# FM_Transmitter.net
KiCad netlist of a schematic drawn in EAGLE
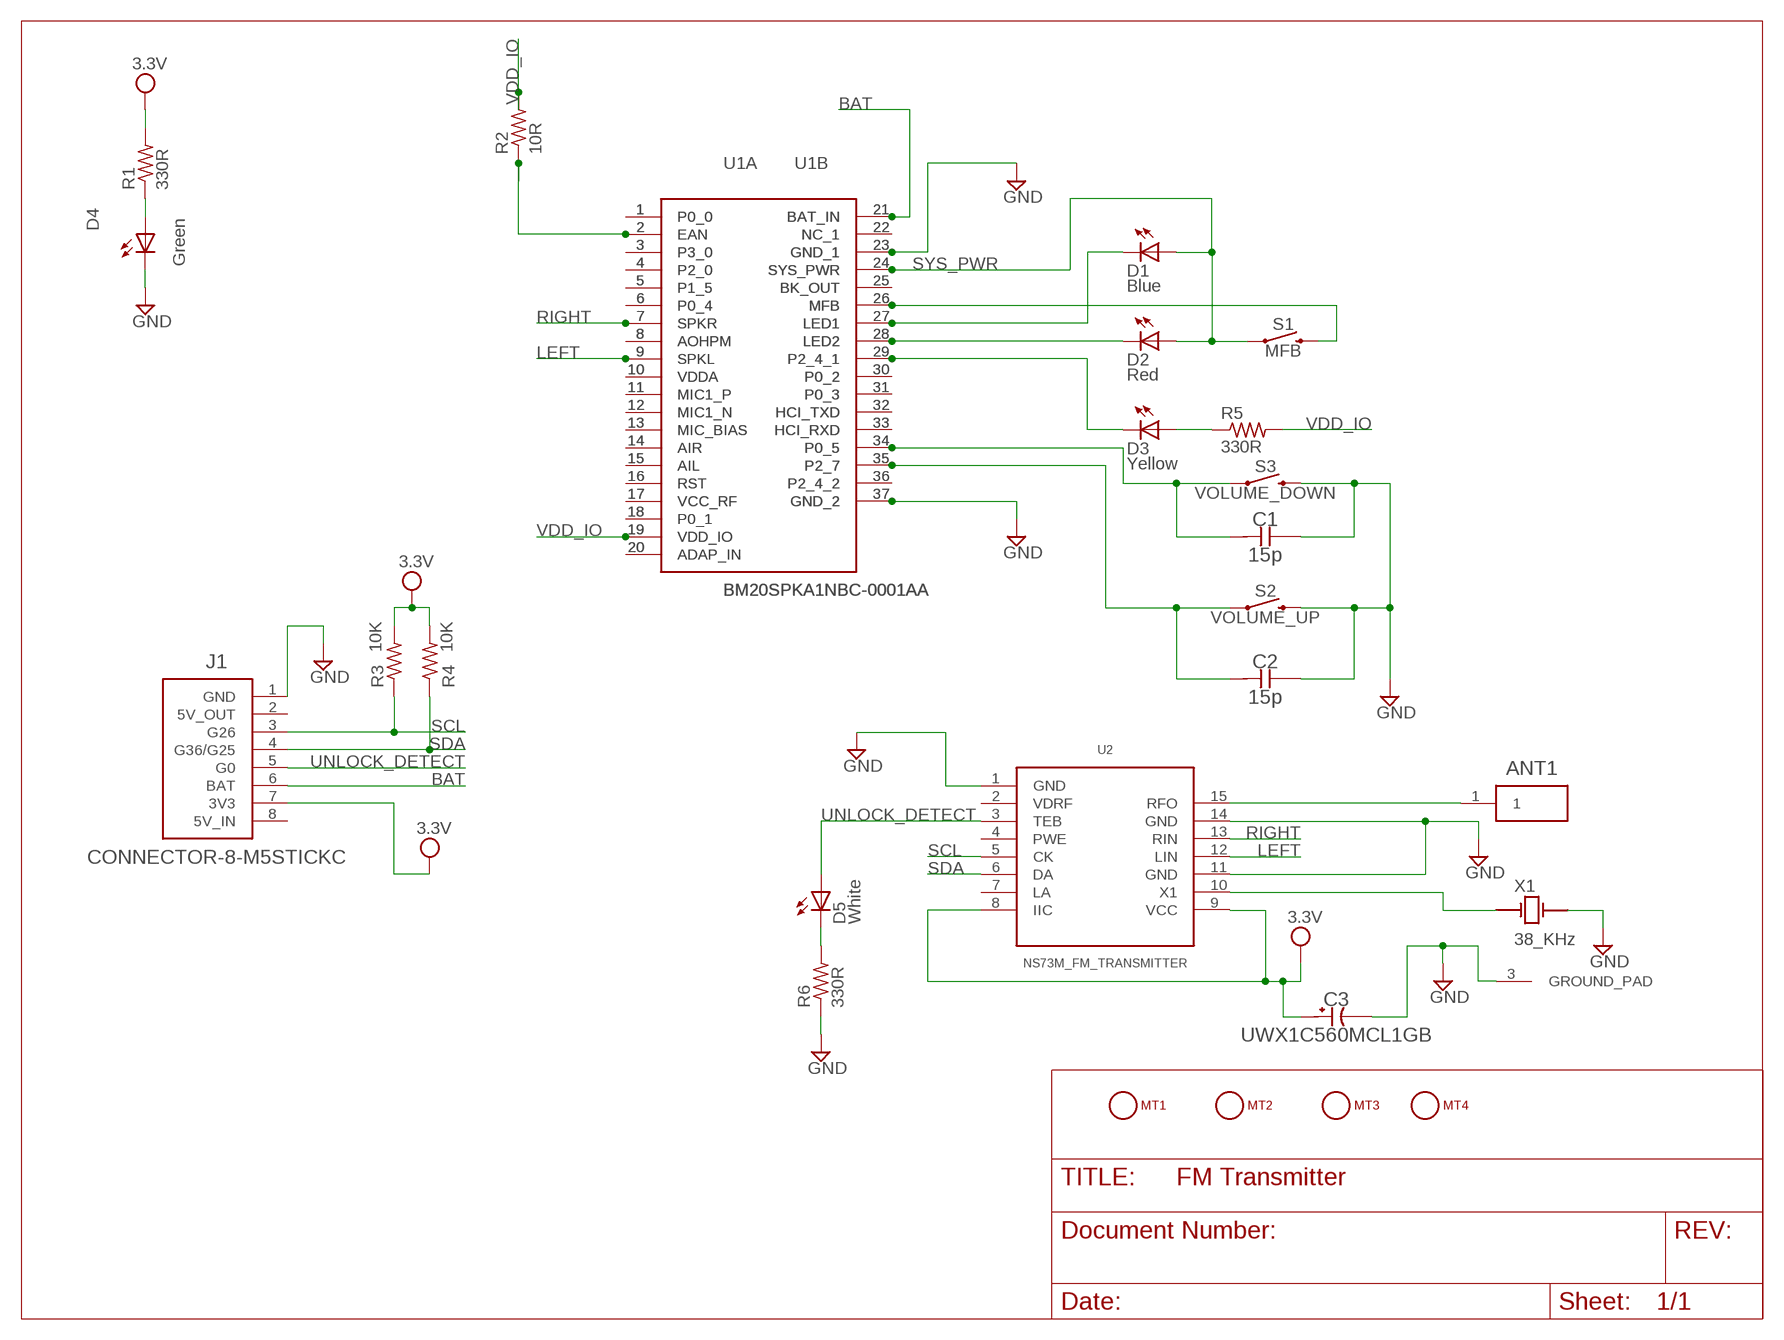
[diagram p0: schematic, sheet 1]

(export (version "E")
  (design (tool "Eeschema 10.0.6"))
  (components
    (comp (ref "ANT1")
      (value "CONNECTOR-1")
      (footprint "eagle-import:ESQ-101-XX-X-S")
      (libsource (lib "eagle-import") (part "CONNECTOR-1"))
    )
    (comp (ref "C1")
      (value "15p")
      (footprint "eagle-import:CAPC2012X140N")
      (libsource (lib "eagle-import") (part "CAPACITOR-0805"))
    )
    (comp (ref "C2")
      (value "15p")
      (footprint "eagle-import:CAPC2012X140N")
      (libsource (lib "eagle-import") (part "CAPACITOR-0805"))
    )
    (comp (ref "C3")
      (value "UWX1C560MCL1GB")
      (footprint "eagle-import:PCAP_6.3X5.4-ELECT-M")
      (libsource (lib "eagle-import") (part "CAPACITOR_POLARIZED-6.3MM"))
    )
    (comp (ref "D1")
      (value "Blue")
      (footprint "eagle-import:LED5MM")
      (libsource (lib "eagle-import") (part "LED5MM"))
    )
    (comp (ref "D2")
      (value "Red")
      (footprint "eagle-import:LED5MM")
      (libsource (lib "eagle-import") (part "LED5MM"))
    )
    (comp (ref "D3")
      (value "Yellow")
      (footprint "eagle-import:LED5MM")
      (libsource (lib "eagle-import") (part "LED5MM"))
    )
    (comp (ref "D4")
      (value "Green")
      (footprint "eagle-import:LED5MM")
      (libsource (lib "eagle-import") (part "LED5MM"))
    )
    (comp (ref "D5")
      (value "White")
      (footprint "eagle-import:LED5MM")
      (libsource (lib "eagle-import") (part "LED5MM"))
    )
    (comp (ref "J1")
      (value "CONNECTOR-8-M5STICKC")
      (footprint "eagle-import:ESQ-108-XX-X-S")
      (libsource (lib "eagle-import") (part "CONNECTOR-8-M5STICKC"))
    )
    (comp (ref "MT1")
      (value "MOUNTING_HOLE-125_250_ROUND")
      (footprint "eagle-import:MT_125_250")
      (libsource (lib "eagle-import") (part "MOUNTING_HOLE-125_250_ROUND"))
    )
    (comp (ref "MT2")
      (value "MOUNTING_HOLE-125_250_ROUND")
      (footprint "eagle-import:MT_125_250")
      (libsource (lib "eagle-import") (part "MOUNTING_HOLE-125_250_ROUND"))
    )
    (comp (ref "MT3")
      (value "MOUNTING_HOLE-125_250_ROUND")
      (footprint "eagle-import:MT_125_250")
      (libsource (lib "eagle-import") (part "MOUNTING_HOLE-125_250_ROUND"))
    )
    (comp (ref "MT4")
      (value "MOUNTING_HOLE-125_250_ROUND")
      (footprint "eagle-import:MT_125_250")
      (libsource (lib "eagle-import") (part "MOUNTING_HOLE-125_250_ROUND"))
    )
    (comp (ref "R1")
      (value "330R")
      (footprint "eagle-import:R0805")
      (libsource (lib "eagle-import") (part "R-US_R0805"))
    )
    (comp (ref "R2")
      (value "10R")
      (footprint "eagle-import:R0805")
      (libsource (lib "eagle-import") (part "R-US_R0805"))
    )
    (comp (ref "R3")
      (value "10K")
      (footprint "eagle-import:R0805")
      (libsource (lib "eagle-import") (part "R-US_R0805"))
    )
    (comp (ref "R4")
      (value "10K")
      (footprint "eagle-import:R0805")
      (libsource (lib "eagle-import") (part "R-US_R0805"))
    )
    (comp (ref "R5")
      (value "330R")
      (footprint "eagle-import:R0805")
      (libsource (lib "eagle-import") (part "R-US_R0805"))
    )
    (comp (ref "R6")
      (value "330R")
      (footprint "eagle-import:R0805")
      (libsource (lib "eagle-import") (part "R-US_R0805"))
    )
    (comp (ref "S1")
      (value "MFB")
      (footprint "eagle-import:TACTILE_SWITCH_PTH_6.0MM")
      (libsource (lib "eagle-import") (part "MOMENTARY-SWITCH-SPST-PTH-6.0MM"))
    )
    (comp (ref "S2")
      (value "VOLUME_UP")
      (footprint "eagle-import:TACTILE_SWITCH_PTH_6.0MM")
      (libsource (lib "eagle-import") (part "MOMENTARY-SWITCH-SPST-PTH-6.0MM"))
    )
    (comp (ref "S3")
      (value "VOLUME_DOWN")
      (footprint "eagle-import:TACTILE_SWITCH_PTH_6.0MM")
      (libsource (lib "eagle-import") (part "MOMENTARY-SWITCH-SPST-PTH-6.0MM"))
    )
    (comp (ref "U1A")
      (value "BM20SPKA1NBC-0001AA")
      (footprint "eagle-import:BM20SPKA1NBC0001AA")
      (fields (field (name "MOUSER_PART_NUMBER") "579-SPKA1NBC-0001AA"))
      (libsource (lib "eagle-import") (part "BM20SPKA1NBC-0001AA"))
    )
    (comp (ref "U1B")
      (value "BM20SPKA1NBC-0001AA")
      (footprint "eagle-import:BM20SPKA1NBC0001AA")
      (fields (field (name "MOUSER_PART_NUMBER") "579-SPKA1NBC-0001AA"))
      (libsource (lib "eagle-import") (part "BM20SPKA1NBC-0001AA"))
    )
    (comp (ref "U2")
      (value "NS73M_FM_TRANSMITTER")
      (footprint "eagle-import:NS73M")
      (libsource (lib "eagle-import") (part "NS73M_FM_TRANSMITTER"))
    )
    (comp (ref "X1")
      (value "38_KHz")
      (footprint "eagle-import:XTAL-WITH-GROUND-PAD")
      (libsource (lib "eagle-import") (part "XTAL_38_KHZ_GROUND_PAD"))
    )
  )
  (nets
    (net (code "1") (name "/BAT") (class "Default")
      (node (ref "J1") (pin "6") (pinfunction "BAT_6") (pintype "bidirectional"))
      (node (ref "U1A") (pin "21") (pinfunction "BAT_IN_21") (pintype "bidirectional"))
      (node (ref "U1B") (pin "21") (pinfunction "BAT_IN_21") (pintype "bidirectional"))
    )
    (net (code "2") (name "/LEFT") (class "Default")
      (node (ref "U1A") (pin "9") (pinfunction "SPKL_9") (pintype "bidirectional"))
      (node (ref "U1B") (pin "9") (pinfunction "SPKL_9") (pintype "bidirectional"))
      (node (ref "U2") (pin "12") (pinfunction "LIN_12") (pintype "bidirectional"))
    )
    (net (code "3") (name "/RIGHT") (class "Default")
      (node (ref "U1A") (pin "7") (pinfunction "SPKR_7") (pintype "bidirectional"))
      (node (ref "U1B") (pin "7") (pinfunction "SPKR_7") (pintype "bidirectional"))
      (node (ref "U2") (pin "13") (pinfunction "RIN_13") (pintype "bidirectional"))
    )
    (net (code "4") (name "/SCL") (class "Default")
      (node (ref "J1") (pin "3") (pinfunction "G26_3") (pintype "bidirectional"))
      (node (ref "R3") (pin "1") (pinfunction "1_1") (pintype "passive"))
      (node (ref "U2") (pin "5") (pinfunction "CK_5") (pintype "bidirectional"))
    )
    (net (code "5") (name "/SDA") (class "Default")
      (node (ref "J1") (pin "4") (pinfunction "G36/G25_4") (pintype "bidirectional"))
      (node (ref "R4") (pin "1") (pinfunction "1_1") (pintype "passive"))
      (node (ref "U2") (pin "6") (pinfunction "DA_6") (pintype "bidirectional"))
    )
    (net (code "6") (name "/SYS_PWR") (class "Default")
      (node (ref "D1") (pin "A") (pinfunction "A_A") (pintype "passive"))
      (node (ref "D2") (pin "A") (pinfunction "A_A") (pintype "passive"))
      (node (ref "S1") (pin "1") (pinfunction "1_1") (pintype "passive"))
      (node (ref "U1A") (pin "24") (pinfunction "SYS_PWR_24") (pintype "bidirectional"))
      (node (ref "U1B") (pin "24") (pinfunction "SYS_PWR_24") (pintype "bidirectional"))
    )
    (net (code "7") (name "/UNLOCK_DETECT") (class "Default")
      (node (ref "D5") (pin "A") (pinfunction "A_A") (pintype "passive"))
      (node (ref "J1") (pin "5") (pinfunction "G0_5") (pintype "bidirectional"))
      (node (ref "U2") (pin "3") (pinfunction "TEB_3") (pintype "bidirectional"))
    )
    (net (code "8") (name "/VDD_IO") (class "Default")
      (node (ref "R2") (pin "2") (pinfunction "2_2") (pintype "passive"))
      (node (ref "R5") (pin "2") (pinfunction "2_2") (pintype "passive"))
      (node (ref "U1A") (pin "19") (pinfunction "VDD_IO_19") (pintype "bidirectional"))
      (node (ref "U1B") (pin "19") (pinfunction "VDD_IO_19") (pintype "bidirectional"))
    )
    (net (code "9") (name "3.3V") (class "Default")
      (node (ref "C3") (pin "1") (pinfunction "1_1") (pintype "bidirectional"))
      (node (ref "J1") (pin "7") (pinfunction "3V3_7") (pintype "bidirectional"))
      (node (ref "R1") (pin "2") (pinfunction "2_2") (pintype "passive"))
      (node (ref "R3") (pin "2") (pinfunction "2_2") (pintype "passive"))
      (node (ref "R4") (pin "2") (pinfunction "2_2") (pintype "passive"))
      (node (ref "U2") (pin "8") (pinfunction "IIC_8") (pintype "bidirectional"))
      (node (ref "U2") (pin "9") (pinfunction "VCC_9") (pintype "bidirectional"))
    )
    (net (code "10") (name "GND") (class "Default")
      (node (ref "C1") (pin "2") (pinfunction "2_2") (pintype "bidirectional"))
      (node (ref "C2") (pin "2") (pinfunction "2_2") (pintype "bidirectional"))
      (node (ref "C3") (pin "2") (pinfunction "2_2") (pintype "bidirectional"))
      (node (ref "D4") (pin "K") (pinfunction "C_K") (pintype "passive"))
      (node (ref "J1") (pin "1") (pinfunction "GND_1") (pintype "bidirectional"))
      (node (ref "R6") (pin "1") (pinfunction "1_1") (pintype "passive"))
      (node (ref "S2") (pin "3") (pinfunction "2_3") (pintype "passive"))
      (node (ref "S3") (pin "3") (pinfunction "2_3") (pintype "passive"))
      (node (ref "U1A") (pin "23") (pinfunction "GND_1_23") (pintype "bidirectional"))
      (node (ref "U1A") (pin "37") (pinfunction "GND_2_37") (pintype "bidirectional"))
      (node (ref "U1B") (pin "23") (pinfunction "GND_1_23") (pintype "bidirectional"))
      (node (ref "U1B") (pin "37") (pinfunction "GND_2_37") (pintype "bidirectional"))
      (node (ref "U2") (pin "1") (pinfunction "GND_1") (pintype "bidirectional"))
      (node (ref "U2") (pin "11") (pinfunction "GND_11") (pintype "bidirectional"))
      (node (ref "U2") (pin "14") (pinfunction "GND_14") (pintype "bidirectional"))
      (node (ref "X1") (pin "2") (pinfunction "2_2") (pintype "passive"))
      (node (ref "X1") (pin "3") (pinfunction "GROUND_PAD_3") (pintype "bidirectional"))
    )
    (net (code "11") (name "Net-(D1-C)") (class "Default")
      (node (ref "D1") (pin "K") (pinfunction "C_K") (pintype "passive"))
      (node (ref "U1A") (pin "27") (pinfunction "LED1_27") (pintype "bidirectional"))
      (node (ref "U1B") (pin "27") (pinfunction "LED1_27") (pintype "bidirectional"))
    )
    (net (code "12") (name "Net-(D2-C)") (class "Default")
      (node (ref "D2") (pin "K") (pinfunction "C_K") (pintype "passive"))
      (node (ref "U1A") (pin "28") (pinfunction "LED2_28") (pintype "bidirectional"))
      (node (ref "U1B") (pin "28") (pinfunction "LED2_28") (pintype "bidirectional"))
    )
    (net (code "13") (name "Net-(D3-C)") (class "Default")
      (node (ref "D3") (pin "K") (pinfunction "C_K") (pintype "passive"))
      (node (ref "U1A") (pin "29") (pinfunction "P2_4_1_29") (pintype "bidirectional"))
      (node (ref "U1B") (pin "29") (pinfunction "P2_4_1_29") (pintype "bidirectional"))
    )
    (net (code "14") (name "Net-(D3-PadA)") (class "Default")
      (node (ref "D3") (pin "A") (pinfunction "A_A") (pintype "passive"))
      (node (ref "R5") (pin "1") (pinfunction "1_1") (pintype "passive"))
    )
    (net (code "15") (name "Net-(D4-PadA)") (class "Default")
      (node (ref "D4") (pin "A") (pinfunction "A_A") (pintype "passive"))
      (node (ref "R1") (pin "1") (pinfunction "1_1") (pintype "passive"))
    )
    (net (code "16") (name "Net-(D5-C)") (class "Default")
      (node (ref "D5") (pin "K") (pinfunction "C_K") (pintype "passive"))
      (node (ref "R6") (pin "2") (pinfunction "2_2") (pintype "passive"))
    )
    (net (code "17") (name "Net-(S1-2)") (class "Default")
      (node (ref "S1") (pin "3") (pinfunction "2_3") (pintype "passive"))
      (node (ref "U1A") (pin "26") (pinfunction "MFB_26") (pintype "bidirectional"))
      (node (ref "U1B") (pin "26") (pinfunction "MFB_26") (pintype "bidirectional"))
    )
    (net (code "18") (name "Net-(U1A-ADAP_IN)") (class "Default")
      (node (ref "U1A") (pin "20") (pinfunction "ADAP_IN_20") (pintype "bidirectional"))
      (node (ref "U1B") (pin "20") (pinfunction "ADAP_IN_20") (pintype "bidirectional"))
    )
    (net (code "19") (name "Net-(U1A-AIL)") (class "Default")
      (node (ref "U1A") (pin "15") (pinfunction "AIL_15") (pintype "bidirectional"))
      (node (ref "U1B") (pin "15") (pinfunction "AIL_15") (pintype "bidirectional"))
    )
    (net (code "20") (name "Net-(U1A-AIR)") (class "Default")
      (node (ref "U1A") (pin "14") (pinfunction "AIR_14") (pintype "bidirectional"))
      (node (ref "U1B") (pin "14") (pinfunction "AIR_14") (pintype "bidirectional"))
    )
    (net (code "21") (name "Net-(U1A-AOHPM)") (class "Default")
      (node (ref "U1A") (pin "8") (pinfunction "AOHPM_8") (pintype "bidirectional"))
      (node (ref "U1B") (pin "8") (pinfunction "AOHPM_8") (pintype "bidirectional"))
    )
    (net (code "22") (name "Net-(U1A-BK_OUT)") (class "Default")
      (node (ref "U1A") (pin "25") (pinfunction "BK_OUT_25") (pintype "bidirectional"))
      (node (ref "U1B") (pin "25") (pinfunction "BK_OUT_25") (pintype "bidirectional"))
    )
    (net (code "23") (name "Net-(U1A-EAN)") (class "Default")
      (node (ref "R2") (pin "1") (pinfunction "1_1") (pintype "passive"))
      (node (ref "U1A") (pin "2") (pinfunction "EAN_2") (pintype "bidirectional"))
      (node (ref "U1B") (pin "2") (pinfunction "EAN_2") (pintype "bidirectional"))
    )
    (net (code "24") (name "Net-(U1A-HCI_RXD)") (class "Default")
      (node (ref "U1A") (pin "33") (pinfunction "HCI_RXD_33") (pintype "bidirectional"))
      (node (ref "U1B") (pin "33") (pinfunction "HCI_RXD_33") (pintype "bidirectional"))
    )
    (net (code "25") (name "Net-(U1A-HCI_TXD)") (class "Default")
      (node (ref "U1A") (pin "32") (pinfunction "HCI_TXD_32") (pintype "bidirectional"))
      (node (ref "U1B") (pin "32") (pinfunction "HCI_TXD_32") (pintype "bidirectional"))
    )
    (net (code "26") (name "Net-(U1A-MIC1_N)") (class "Default")
      (node (ref "U1A") (pin "12") (pinfunction "MIC1_N_12") (pintype "bidirectional"))
      (node (ref "U1B") (pin "12") (pinfunction "MIC1_N_12") (pintype "bidirectional"))
    )
    (net (code "27") (name "Net-(U1A-MIC1_P)") (class "Default")
      (node (ref "U1A") (pin "11") (pinfunction "MIC1_P_11") (pintype "bidirectional"))
      (node (ref "U1B") (pin "11") (pinfunction "MIC1_P_11") (pintype "bidirectional"))
    )
    (net (code "28") (name "Net-(U1A-MIC_BIAS)") (class "Default")
      (node (ref "U1A") (pin "13") (pinfunction "MIC_BIAS_13") (pintype "bidirectional"))
      (node (ref "U1B") (pin "13") (pinfunction "MIC_BIAS_13") (pintype "bidirectional"))
    )
    (net (code "29") (name "Net-(U1A-NC_1)") (class "Default")
      (node (ref "U1A") (pin "22") (pinfunction "NC_1_22") (pintype "bidirectional"))
      (node (ref "U1B") (pin "22") (pinfunction "NC_1_22") (pintype "bidirectional"))
    )
    (net (code "30") (name "Net-(U1A-P0_0)") (class "Default")
      (node (ref "U1A") (pin "1") (pinfunction "P0_0_1") (pintype "bidirectional"))
      (node (ref "U1B") (pin "1") (pinfunction "P0_0_1") (pintype "bidirectional"))
    )
    (net (code "31") (name "Net-(U1A-P0_1)") (class "Default")
      (node (ref "U1A") (pin "18") (pinfunction "P0_1_18") (pintype "bidirectional"))
      (node (ref "U1B") (pin "18") (pinfunction "P0_1_18") (pintype "bidirectional"))
    )
    (net (code "32") (name "Net-(U1A-P0_2)") (class "Default")
      (node (ref "U1A") (pin "30") (pinfunction "P0_2_30") (pintype "bidirectional"))
      (node (ref "U1B") (pin "30") (pinfunction "P0_2_30") (pintype "bidirectional"))
    )
    (net (code "33") (name "Net-(U1A-P0_3)") (class "Default")
      (node (ref "U1A") (pin "31") (pinfunction "P0_3_31") (pintype "bidirectional"))
      (node (ref "U1B") (pin "31") (pinfunction "P0_3_31") (pintype "bidirectional"))
    )
    (net (code "34") (name "Net-(U1A-P0_4)") (class "Default")
      (node (ref "U1A") (pin "6") (pinfunction "P0_4_6") (pintype "bidirectional"))
      (node (ref "U1B") (pin "6") (pinfunction "P0_4_6") (pintype "bidirectional"))
    )
    (net (code "35") (name "Net-(U1A-P0_5)") (class "Default")
      (node (ref "C1") (pin "1") (pinfunction "1_1") (pintype "bidirectional"))
      (node (ref "S3") (pin "1") (pinfunction "1_1") (pintype "passive"))
      (node (ref "U1A") (pin "34") (pinfunction "P0_5_34") (pintype "bidirectional"))
      (node (ref "U1B") (pin "34") (pinfunction "P0_5_34") (pintype "bidirectional"))
    )
    (net (code "36") (name "Net-(U1A-P1_5)") (class "Default")
      (node (ref "U1A") (pin "5") (pinfunction "P1_5_5") (pintype "bidirectional"))
      (node (ref "U1B") (pin "5") (pinfunction "P1_5_5") (pintype "bidirectional"))
    )
    (net (code "37") (name "Net-(U1A-P2_0)") (class "Default")
      (node (ref "U1A") (pin "4") (pinfunction "P2_0_4") (pintype "bidirectional"))
      (node (ref "U1B") (pin "4") (pinfunction "P2_0_4") (pintype "bidirectional"))
    )
    (net (code "38") (name "Net-(U1A-P2_4_2)") (class "Default")
      (node (ref "U1A") (pin "36") (pinfunction "P2_4_2_36") (pintype "bidirectional"))
      (node (ref "U1B") (pin "36") (pinfunction "P2_4_2_36") (pintype "bidirectional"))
    )
    (net (code "39") (name "Net-(U1A-P2_7)") (class "Default")
      (node (ref "C2") (pin "1") (pinfunction "1_1") (pintype "bidirectional"))
      (node (ref "S2") (pin "1") (pinfunction "1_1") (pintype "passive"))
      (node (ref "U1A") (pin "35") (pinfunction "P2_7_35") (pintype "bidirectional"))
      (node (ref "U1B") (pin "35") (pinfunction "P2_7_35") (pintype "bidirectional"))
    )
    (net (code "40") (name "Net-(U1A-P3_0)") (class "Default")
      (node (ref "U1A") (pin "3") (pinfunction "P3_0_3") (pintype "bidirectional"))
      (node (ref "U1B") (pin "3") (pinfunction "P3_0_3") (pintype "bidirectional"))
    )
    (net (code "41") (name "Net-(U1A-RST)") (class "Default")
      (node (ref "U1A") (pin "16") (pinfunction "RST_16") (pintype "bidirectional"))
      (node (ref "U1B") (pin "16") (pinfunction "RST_16") (pintype "bidirectional"))
    )
    (net (code "42") (name "Net-(U1A-VCC_RF)") (class "Default")
      (node (ref "U1A") (pin "17") (pinfunction "VCC_RF_17") (pintype "bidirectional"))
      (node (ref "U1B") (pin "17") (pinfunction "VCC_RF_17") (pintype "bidirectional"))
    )
    (net (code "43") (name "Net-(U1A-VDDA)") (class "Default")
      (node (ref "U1A") (pin "10") (pinfunction "VDDA_10") (pintype "bidirectional"))
      (node (ref "U1B") (pin "10") (pinfunction "VDDA_10") (pintype "bidirectional"))
    )
    (net (code "44") (name "Net-(U2-RFO)") (class "Default")
      (node (ref "ANT1") (pin "1") (pinfunction "1_1") (pintype "bidirectional"))
      (node (ref "U2") (pin "15") (pinfunction "RFO_15") (pintype "bidirectional"))
    )
    (net (code "45") (name "Net-(U2-X1)") (class "Default")
      (node (ref "U2") (pin "10") (pinfunction "X1_10") (pintype "bidirectional"))
      (node (ref "X1") (pin "1") (pinfunction "1_1") (pintype "passive"))
    )
    (net (code "46") (name "unconnected-(J1-5V_IN-Pad8)") (class "Default")
      (node (ref "J1") (pin "8") (pinfunction "5V_IN_8") (pintype "bidirectional"))
    )
    (net (code "47") (name "unconnected-(J1-5V_OUT-Pad2)") (class "Default")
      (node (ref "J1") (pin "2") (pinfunction "5V_OUT_2") (pintype "bidirectional"))
    )
    (net (code "48") (name "unconnected-(MT1-P$1-Pad1)") (class "Default")
      (node (ref "MT1") (pin "1") (pinfunction "P$1_1") (pintype "bidirectional"))
    )
    (net (code "49") (name "unconnected-(MT2-P$1-Pad1)") (class "Default")
      (node (ref "MT2") (pin "1") (pinfunction "P$1_1") (pintype "bidirectional"))
    )
    (net (code "50") (name "unconnected-(MT3-P$1-Pad1)") (class "Default")
      (node (ref "MT3") (pin "1") (pinfunction "P$1_1") (pintype "bidirectional"))
    )
    (net (code "51") (name "unconnected-(MT4-P$1-Pad1)") (class "Default")
      (node (ref "MT4") (pin "1") (pinfunction "P$1_1") (pintype "bidirectional"))
    )
    (net (code "52") (name "unconnected-(U2-LA-Pad7)") (class "Default")
      (node (ref "U2") (pin "7") (pinfunction "LA_7") (pintype "bidirectional"))
    )
    (net (code "53") (name "unconnected-(U2-PWE-Pad4)") (class "Default")
      (node (ref "U2") (pin "4") (pinfunction "PWE_4") (pintype "bidirectional"))
    )
    (net (code "54") (name "unconnected-(U2-VDRF-Pad2)") (class "Default")
      (node (ref "U2") (pin "2") (pinfunction "VDRF_2") (pintype "bidirectional"))
    )
  )
)
